# 7_HDMI.net
KiCad netlist of a schematic drawn in Altium Designer
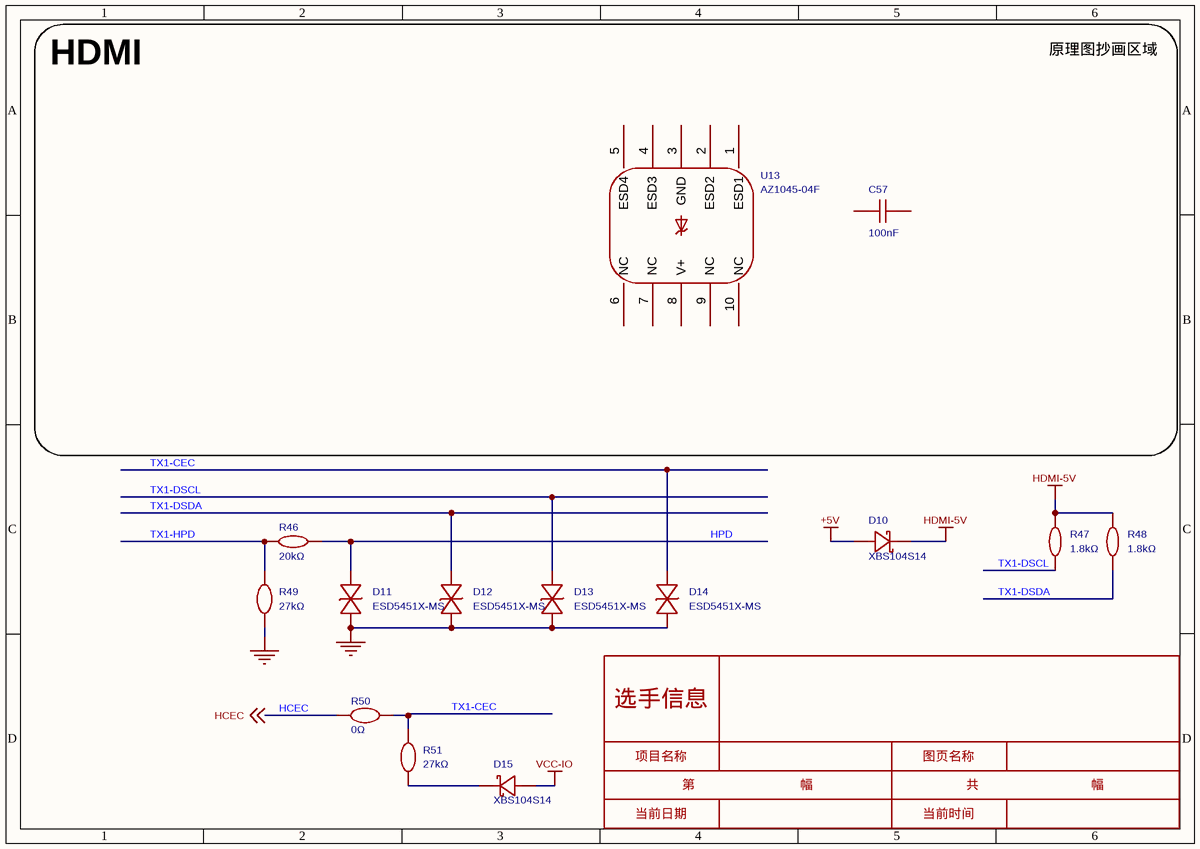
[diagram p0: 7_HDMI.schdoc]

(export (version "E")
  (design (tool "Eeschema 10.0.6"))
  (components
    (comp (ref "C57")
      (value "100nF")
      (footprint "C0402")
      (description "容值:100nF;精度:±10%;额定电压:16V;温度系数:X7R;")
      (fields
        (field (name "MANUFACTURER") "SAMSUNG(三星)")
        (field (name "MANUFACTURER PART") "CL05B104KO5NNNC")
      )
      (libsource (lib "altium-import") (part "root_2_CL05B104KO5NNNC_"))
    )
    (comp (ref "D10")
      (value "XBS104S14")
      (footprint "SOD-123FL_L2.8-W1.8-LS3.7-RD")
      (description "二极管配置:独立式;正向压降(Vf):490mV@1A;直流反向耐压(Vr):40V;整流电流:1A;")
      (fields (field (name "MANUFACTURER") "Slkor(萨科微)"))
      (libsource (lib "altium-import") (part "root_2_XBS104S14_"))
    )
    (comp (ref "D11")
      (value "ESD5451X-MS")
      (footprint "DFN1006-2L-BI")
      (description "反向截止电压(Vrwm):5V;峰值脉冲电流(Ipp):8A;击穿电压:5.6V;")
      (fields (field (name "MANUFACTURER") "MSKSEMI(美森科)"))
      (libsource (lib "altium-import") (part "root_1_ESD5451X-MS_"))
    )
    (comp (ref "D12")
      (value "ESD5451X-MS")
      (footprint "DFN1006-2L-BI")
      (description "反向截止电压(Vrwm):5V;峰值脉冲电流(Ipp):8A;击穿电压:5.6V;")
      (fields (field (name "MANUFACTURER") "MSKSEMI(美森科)"))
      (libsource (lib "altium-import") (part "root_1_ESD5451X-MS_"))
    )
    (comp (ref "D13")
      (value "ESD5451X-MS")
      (footprint "DFN1006-2L-BI")
      (description "反向截止电压(Vrwm):5V;峰值脉冲电流(Ipp):8A;击穿电压:5.6V;")
      (fields (field (name "MANUFACTURER") "MSKSEMI(美森科)"))
      (libsource (lib "altium-import") (part "root_1_ESD5451X-MS_"))
    )
    (comp (ref "D14")
      (value "ESD5451X-MS")
      (footprint "DFN1006-2L-BI")
      (description "反向截止电压(Vrwm):5V;峰值脉冲电流(Ipp):8A;击穿电压:5.6V;")
      (fields (field (name "MANUFACTURER") "MSKSEMI(美森科)"))
      (libsource (lib "altium-import") (part "root_1_ESD5451X-MS_"))
    )
    (comp (ref "D15")
      (value "XBS104S14")
      (footprint "SOD-123FL_L2.8-W1.8-LS3.7-RD")
      (description "二极管配置:独立式;正向压降(Vf):490mV@1A;直流反向耐压(Vr):40V;整流电流:1A;")
      (fields (field (name "MANUFACTURER") "Slkor(萨科微)"))
      (libsource (lib "altium-import") (part "root_0_XBS104S14_"))
    )
    (comp (ref "R46")
      (value "20kΩ")
      (footprint "R0402")
      (description "电阻类型:厚膜电阻;阻值:20kΩ;精度:±1%;功率:62.5mW;工作电压:50V;温度系数:±100ppm/℃;")
      (fields (field (name "MANUFACTURER") "FOJAN(富捷)") (field (name "MANUFACTURER PART") "FRC0402F2002TS"))
      (libsource (lib "altium-import") (part "root_0_FRC0402F2002TS_"))
    )
    (comp (ref "R47")
      (value "1.8kΩ")
      (footprint "R0402")
      (description "电阻类型:厚膜电阻;阻值:1.8kΩ;精度:±1%;功率:62.5mW;工作电压:50V;温度系数:±100ppm/℃;")
      (fields
        (field (name "MANUFACTURER") "UNI-ROYAL(厚声)")
        (field (name "MANUFACTURER PART") "0402WGF1801TCE")
      )
      (libsource (lib "altium-import") (part "root_1_0402WGF1801TCE_"))
    )
    (comp (ref "R48")
      (value "1.8kΩ")
      (footprint "R0402")
      (description "电阻类型:厚膜电阻;阻值:1.8kΩ;精度:±1%;功率:62.5mW;工作电压:50V;温度系数:±100ppm/℃;")
      (fields
        (field (name "MANUFACTURER") "UNI-ROYAL(厚声)")
        (field (name "MANUFACTURER PART") "0402WGF1801TCE")
      )
      (libsource (lib "altium-import") (part "root_1_0402WGF1801TCE_"))
    )
    (comp (ref "R49")
      (value "27kΩ")
      (footprint "R0402")
      (description "电阻类型:厚膜电阻;阻值:27kΩ;精度:±1%;功率:62.5mW;工作电压:50V;温度系数:±100ppm/℃;")
      (fields (field (name "MANUFACTURER") "FOJAN(富捷)") (field (name "MANUFACTURER PART") "FRC0402F2702TS"))
      (libsource (lib "altium-import") (part "root_1_FRC0402F2702TS_"))
    )
    (comp (ref "R50")
      (value "0Ω")
      (footprint "R0402")
      (description "电阻类型:厚膜电阻;阻值:0Ω;精度:±5%;功率:62.5mW;工作电压:50V;")
      (fields (field (name "MANUFACTURER") "FOJAN(富捷)") (field (name "MANUFACTURER PART") "FRC0402P000 TS"))
      (libsource (lib "altium-import") (part "root_0_FRC0402P000 TS_"))
    )
    (comp (ref "R51")
      (value "27kΩ")
      (footprint "R0402")
      (description "电阻类型:厚膜电阻;阻值:27kΩ;精度:±1%;功率:62.5mW;工作电压:50V;温度系数:±100ppm/℃;")
      (fields (field (name "MANUFACTURER") "FOJAN(富捷)") (field (name "MANUFACTURER PART") "FRC0402F2702TS"))
      (libsource (lib "altium-import") (part "root_1_FRC0402F2702TS_"))
    )
    (comp (ref "U13")
      (value "AZ1045-04F")
      (footprint "DFN2510-10_L2.5-W1.0-P0.50-BL")
      (libsource (lib "altium-import") (part "root_3_AZ1045-04F_"))
    )
  )
  (nets
    (net (code "1") (name "+5V") (class "Default")
      (node (ref "D10") (pin "2") (pinfunction "A_2") (pintype "passive"))
    )
    (net (code "3") (name "/HPD") (class "Default")
      (node (ref "D11") (pin "2") (pinfunction "2_2") (pintype "passive"))
      (node (ref "R46") (pin "2") (pinfunction "2_2") (pintype "passive"))
    )
    (net (code "4") (name "/TX1-CEC") (class "Default")
      (node (ref "D14") (pin "2") (pinfunction "2_2") (pintype "passive"))
      (node (ref "R50") (pin "2") (pinfunction "2_2") (pintype "passive"))
      (node (ref "R51") (pin "2") (pinfunction "2_2") (pintype "passive"))
    )
    (net (code "5") (name "/TX1-DSCL") (class "Default")
      (node (ref "D13") (pin "2") (pinfunction "2_2") (pintype "passive"))
      (node (ref "R47") (pin "1") (pinfunction "1_1") (pintype "passive"))
    )
    (net (code "6") (name "/TX1-DSDA") (class "Default")
      (node (ref "D12") (pin "2") (pinfunction "2_2") (pintype "passive"))
      (node (ref "R48") (pin "1") (pinfunction "1_1") (pintype "passive"))
    )
    (net (code "7") (name "/TX1-HPD") (class "Default")
      (node (ref "R46") (pin "1") (pinfunction "1_1") (pintype "passive"))
      (node (ref "R49") (pin "2") (pinfunction "2_2") (pintype "passive"))
    )
    (net (code "8") (name "GND") (class "Default")
      (node (ref "D11") (pin "1") (pinfunction "1_1") (pintype "passive"))
      (node (ref "D12") (pin "1") (pinfunction "1_1") (pintype "passive"))
      (node (ref "D13") (pin "1") (pinfunction "1_1") (pintype "passive"))
      (node (ref "D14") (pin "1") (pinfunction "1_1") (pintype "passive"))
      (node (ref "R49") (pin "1") (pinfunction "1_1") (pintype "passive"))
    )
    (net (code "9") (name "HCEC") (class "Default")
      (node (ref "R50") (pin "1") (pinfunction "1_1") (pintype "passive"))
    )
    (net (code "10") (name "HDMI-5V") (class "Default")
      (node (ref "D10") (pin "1") (pinfunction "K_1") (pintype "passive"))
      (node (ref "R47") (pin "2") (pinfunction "2_2") (pintype "passive"))
      (node (ref "R48") (pin "2") (pinfunction "2_2") (pintype "passive"))
    )
    (net (code "11") (name "Net-(D15-K)") (class "Default")
      (node (ref "D15") (pin "1") (pinfunction "K_1") (pintype "passive"))
      (node (ref "R51") (pin "1") (pinfunction "1_1") (pintype "passive"))
    )
    (net (code "12") (name "VCC-IO") (class "Default")
      (node (ref "D15") (pin "2") (pinfunction "A_2") (pintype "passive"))
    )
    (net (code "13") (name "unconnected-(C57-Pad1)") (class "Default")
      (node (ref "C57") (pin "1") (pinfunction "1_1") (pintype "passive"))
    )
    (net (code "14") (name "unconnected-(C57-Pad2)") (class "Default")
      (node (ref "C57") (pin "2") (pinfunction "2_2") (pintype "passive"))
    )
    (net (code "15") (name "unconnected-(U13-ESD1-Pad1)") (class "Default")
      (node (ref "U13") (pin "1") (pinfunction "ESD1_1") (pintype "passive"))
    )
    (net (code "16") (name "unconnected-(U13-ESD2-Pad2)") (class "Default")
      (node (ref "U13") (pin "2") (pinfunction "ESD2_2") (pintype "passive"))
    )
    (net (code "17") (name "unconnected-(U13-ESD3-Pad4)") (class "Default")
      (node (ref "U13") (pin "4") (pinfunction "ESD3_4") (pintype "passive"))
    )
    (net (code "18") (name "unconnected-(U13-ESD4-Pad5)") (class "Default")
      (node (ref "U13") (pin "5") (pinfunction "ESD4_5") (pintype "passive"))
    )
    (net (code "19") (name "unconnected-(U13-GND-Pad3)") (class "Default")
      (node (ref "U13") (pin "3") (pinfunction "GND_3") (pintype "passive"))
    )
    (net (code "20") (name "unconnected-(U13-NC-Pad6)") (class "Default")
      (node (ref "U13") (pin "6") (pinfunction "NC_6") (pintype "passive"))
    )
    (net (code "21") (name "unconnected-(U13-NC-Pad7)") (class "Default")
      (node (ref "U13") (pin "7") (pinfunction "NC_7") (pintype "passive"))
    )
    (net (code "22") (name "unconnected-(U13-NC-Pad9)") (class "Default")
      (node (ref "U13") (pin "9") (pinfunction "NC_9") (pintype "passive"))
    )
    (net (code "23") (name "unconnected-(U13-NC-Pad10)") (class "Default")
      (node (ref "U13") (pin "10") (pinfunction "NC_10") (pintype "passive"))
    )
    (net (code "24") (name "unconnected-(U13-V+-Pad8)") (class "Default")
      (node (ref "U13") (pin "8") (pinfunction "V+_8") (pintype "passive"))
    )
  )
)
